# BMS_AFE_-_Thermistors.net
KiCad netlist of a schematic drawn in Altium Designer
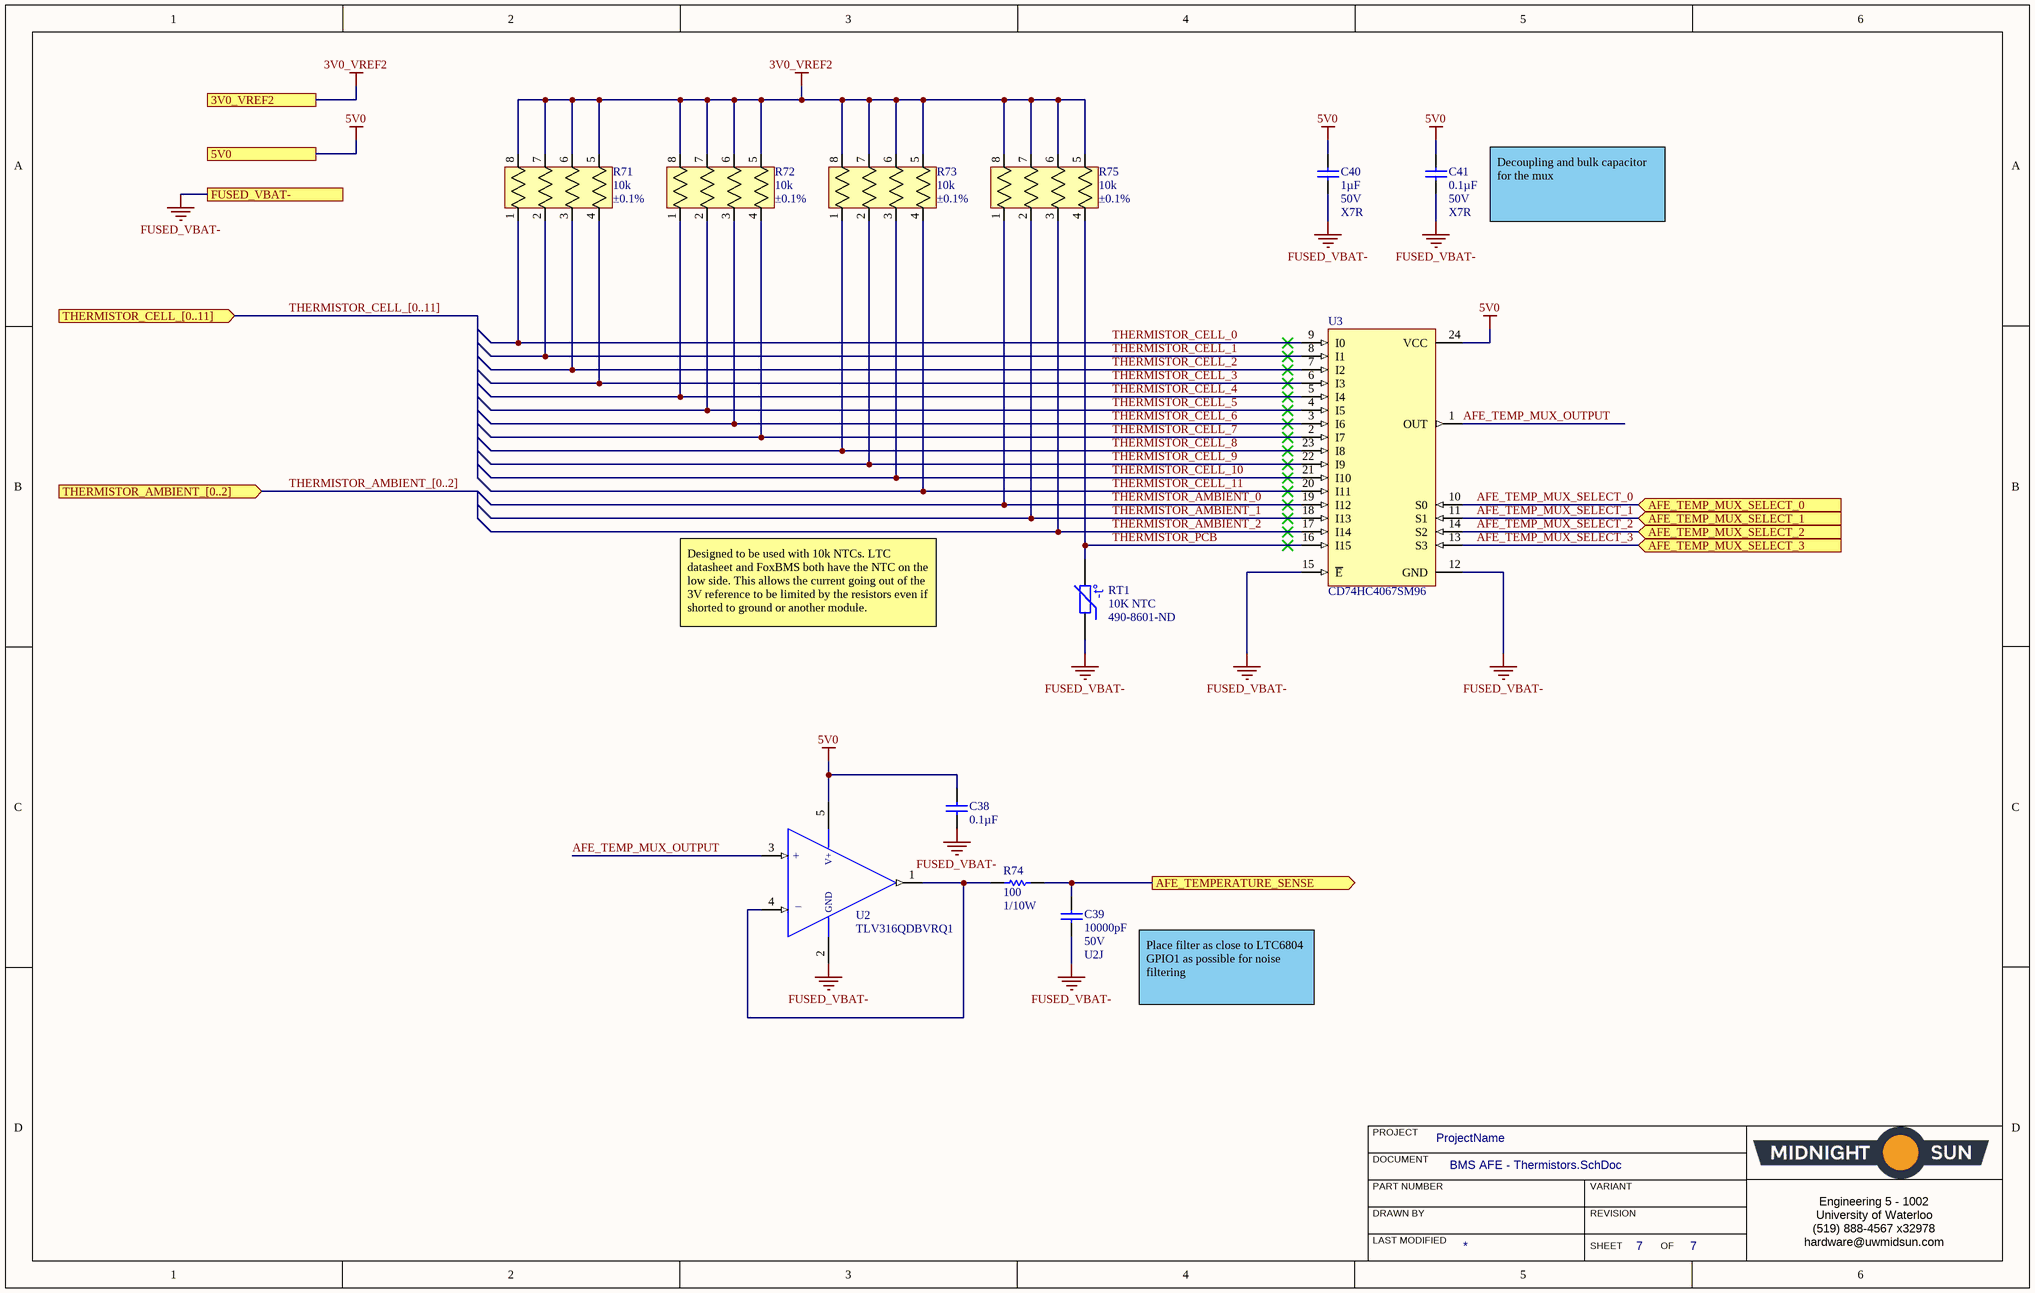
[diagram p0: BMS AFE - Thermistors.SchDoc]

(export (version "E")
  (design (tool "Eeschema 10.0.6"))
  (components
    (comp (ref "C38")
      (value "CAP CER 0.1UF 50V 10% X7R 0603")
      (footprint "CAP, 0603")
      (description "0.10µF ±10% 50V Ceramic Capacitor X7R 0603 (1608 Metric)")
      (fields
        (field (name "TOLERANCE") "±10%")
        (field (name "CAPACITANCE") "0.1µF")
        (field (name "VOLTAGE") "50V")
      )
      (libsource (lib "Schematic Diagrams") (part "CAP CER 0.1UF 50V 10% X7R 0603"))
    )
    (comp (ref "C39")
      (value "CAP CER 10nF 50V 5% X7R 0603")
      (footprint "CAP, 0603")
      (description "10000pF ±5% 50V Ceramic Capacitor U2J 0603 (1608 Metric)")
      (fields
        (field (name "TOLERANCE") "±5%")
        (field (name "CAPACITANCE") "10000pF")
        (field (name "VOLTAGE") "50V")
        (field (name "TEMPERATURE COEFFICIENT") "U2J")
      )
      (libsource (lib "Schematic Diagrams") (part "CAP CER 10nF 50V 5% X7R 0603"))
    )
    (comp (ref "C40")
      (value "CAP CER 1UF 50V 10% X7R 0603")
      (footprint "CAP, 0603")
      (description "1µF ±10% 50V Ceramic Capacitor X7R 0603 (1608 Metric)")
      (fields
        (field (name "TOLERANCE") "±10%")
        (field (name "CAPACITANCE") "1µF")
        (field (name "VOLTAGE") "50V")
        (field (name "TEMPERATURE COEFFICIENT") "X7R")
      )
      (libsource (lib "Schematic Diagrams") (part "CAP CER 1UF 50V 10% X7R 0603"))
    )
    (comp (ref "C41")
      (value "CAP CER 0.1UF 50V 10% X7R 0603")
      (footprint "CAP, 0603")
      (description "0.10µF ±10% 50V Ceramic Capacitor X7R 0603 (1608 Metric)")
      (fields
        (field (name "TOLERANCE") "±10%")
        (field (name "CAPACITANCE") "0.1µF")
        (field (name "VOLTAGE") "50V")
        (field (name "TEMPERATURE COEFFICIENT") "X7R")
      )
      (libsource (lib "Schematic Diagrams") (part "CAP CER 0.1UF 50V 10% X7R 0603"))
    )
    (comp (ref "R71")
      (value "RES ARRAY 10K OHM 0.1% 4RES 1206")
      (footprint "RES ARRAY 4RES 1206")
      (fields
        (field (name "MANUFACTURER") "Vishay Beyschlag")
        (field (name "MANUFACTURER PART NUMBER") "ACASA1002S1002P100")
        (field (name "RESISTANCE (OHMS)") "10k")
        (field (name "TOLERANCE") "±0.1%")
      )
      (libsource (lib "Schematic Diagrams") (part "RES ARRAY 10K OHM 0.1% 4RES 1206"))
    )
    (comp (ref "R72")
      (value "RES ARRAY 10K OHM 0.1% 4RES 1206")
      (footprint "RES ARRAY 4RES 1206")
      (fields
        (field (name "MANUFACTURER") "Vishay Beyschlag")
        (field (name "MANUFACTURER PART NUMBER") "ACASA1002S1002P100")
        (field (name "RESISTANCE (OHMS)") "10k")
        (field (name "TOLERANCE") "±0.1%")
      )
      (libsource (lib "Schematic Diagrams") (part "RES ARRAY 10K OHM 0.1% 4RES 1206"))
    )
    (comp (ref "R73")
      (value "RES ARRAY 10K OHM 0.1% 4RES 1206")
      (footprint "RES ARRAY 4RES 1206")
      (fields
        (field (name "MANUFACTURER") "Vishay Beyschlag")
        (field (name "MANUFACTURER PART NUMBER") "ACASA1002S1002P100")
        (field (name "RESISTANCE (OHMS)") "10k")
        (field (name "TOLERANCE") "±0.1%")
      )
      (libsource (lib "Schematic Diagrams") (part "RES ARRAY 10K OHM 0.1% 4RES 1206"))
    )
    (comp (ref "R74")
      (value "RES 100 OHM 1% 1/10W 0603")
      (footprint "RES, 0603")
      (description "100 Ohm ±1% 0.1W, 1/10W Chip Resistor 0603 (1608 Metric) Moisture Resistant Thick Film")
      (fields
        (field (name "TOLERANCE") "±1%")
        (field (name "RESISTANCE") "100")
        (field (name "POWER") "1/10W")
      )
      (libsource (lib "Schematic Diagrams") (part "RES 100 OHM 1% 1/10W 0603"))
    )
    (comp (ref "R75")
      (value "RES ARRAY 10K OHM 0.1% 4RES 1206")
      (footprint "RES ARRAY 4RES 1206")
      (fields
        (field (name "MANUFACTURER") "Vishay Beyschlag")
        (field (name "MANUFACTURER PART NUMBER") "ACASA1002S1002P100")
        (field (name "RESISTANCE (OHMS)") "10k")
        (field (name "TOLERANCE") "±0.1%")
      )
      (libsource (lib "Schematic Diagrams") (part "RES ARRAY 10K OHM 0.1% 4RES 1206"))
    )
    (comp (ref "RT1")
      (value "10K NTC")
      (footprint "NTC THERMISTOR BEAD")
      (description "NTC Thermistor 10k Bead")
      (fields
        (field (name "MANUFACTURER") "Murata Electronics North America")
        (field (name "MANUFACTURER PART NUMBER") "NXRT15XH103FA1B030")
        (field (name "SUPPLIER PART NUMBER 1") "490-8601-ND")
      )
      (libsource (lib "Schematic Diagrams") (part "NTC THERMISTOR 10K 1% BEAD"))
    )
    (comp (ref "U2")
      (value "IC OP AMP GEN PURPOSE RR 10MHZ SOT-23-5")
      (footprint "IC OP AMP GP RR 10MHZ SOT-23-5")
      (description "General Purpose Amplifier 1 Circuit Rail-to-Rail SOT-23-5")
      (fields (field (name "MANUFACTURER PART NUMBER 1") "TLV316QDBVRQ1"))
      (libsource (lib "Schematic Diagrams") (part "IC OP AMP GEN PURPOSE RR 10MHZ SOT-23-5"))
    )
    (comp (ref "U3")
      (value "IC MUX/DEMUX 1X16 24SSOP")
      (footprint "SOP127P1030X265-24N")
      (description "1 Circuit IC Switch 16:1 160 Ohm 24-SSOP")
      (fields (field (name "MANUFACTURER PART NUMBER 1") "CD74HC4067SM96"))
      (libsource (lib "Schematic Diagrams") (part "IC MUX/DEMUX 1X16 24SSOP"))
    )
  )
  (nets
    (net (code "1") (name "/AFE_TEMPERATURE_SENSE") (class "Default")
      (node (ref "C39") (pin "1") (pinfunction "1_1") (pintype "passive"))
      (node (ref "R74") (pin "2") (pinfunction "2_2") (pintype "passive"))
    )
    (net (code "2") (name "/AFE_TEMP_MUX_OUTPUT") (class "Default")
      (node (ref "U2") (pin "3") (pinfunction "+IN_3") (pintype "input"))
      (node (ref "U3") (pin "1") (pinfunction "OUT_1") (pintype "output"))
    )
    (net (code "3") (name "/AFE_TEMP_MUX_SELECT_0") (class "Default")
      (node (ref "U3") (pin "10") (pinfunction "S0_10") (pintype "input"))
    )
    (net (code "4") (name "/AFE_TEMP_MUX_SELECT_1") (class "Default")
      (node (ref "U3") (pin "11") (pinfunction "S1_11") (pintype "input"))
    )
    (net (code "5") (name "/AFE_TEMP_MUX_SELECT_2") (class "Default")
      (node (ref "U3") (pin "14") (pinfunction "S2_14") (pintype "input"))
    )
    (net (code "6") (name "/AFE_TEMP_MUX_SELECT_3") (class "Default")
      (node (ref "U3") (pin "13") (pinfunction "S3_13") (pintype "input"))
    )
    (net (code "7") (name "/THERMISTOR_AMBIENT_0") (class "Default")
      (node (ref "R75") (pin "1") (pinfunction "1_1") (pintype "passive"))
      (node (ref "U3") (pin "19") (pinfunction "I12_19") (pintype "input"))
    )
    (net (code "8") (name "/THERMISTOR_AMBIENT_1") (class "Default")
      (node (ref "R75") (pin "2") (pinfunction "2_2") (pintype "passive"))
      (node (ref "U3") (pin "18") (pinfunction "I13_18") (pintype "input"))
    )
    (net (code "9") (name "/THERMISTOR_AMBIENT_2") (class "Default")
      (node (ref "R75") (pin "3") (pinfunction "3_3") (pintype "passive"))
      (node (ref "U3") (pin "17") (pinfunction "I14_17") (pintype "input"))
    )
    (net (code "11") (name "/THERMISTOR_CELL_0") (class "Default")
      (node (ref "R71") (pin "1") (pinfunction "1_1") (pintype "passive"))
      (node (ref "U3") (pin "9") (pinfunction "I0_9") (pintype "input"))
    )
    (net (code "12") (name "/THERMISTOR_CELL_1") (class "Default")
      (node (ref "R71") (pin "2") (pinfunction "2_2") (pintype "passive"))
      (node (ref "U3") (pin "8") (pinfunction "I1_8") (pintype "input"))
    )
    (net (code "13") (name "/THERMISTOR_CELL_2") (class "Default")
      (node (ref "R71") (pin "3") (pinfunction "3_3") (pintype "passive"))
      (node (ref "U3") (pin "7") (pinfunction "I2_7") (pintype "input"))
    )
    (net (code "14") (name "/THERMISTOR_CELL_3") (class "Default")
      (node (ref "R71") (pin "4") (pinfunction "4_4") (pintype "passive"))
      (node (ref "U3") (pin "6") (pinfunction "I3_6") (pintype "input"))
    )
    (net (code "15") (name "/THERMISTOR_CELL_4") (class "Default")
      (node (ref "R72") (pin "1") (pinfunction "1_1") (pintype "passive"))
      (node (ref "U3") (pin "5") (pinfunction "I4_5") (pintype "input"))
    )
    (net (code "16") (name "/THERMISTOR_CELL_5") (class "Default")
      (node (ref "R72") (pin "2") (pinfunction "2_2") (pintype "passive"))
      (node (ref "U3") (pin "4") (pinfunction "I5_4") (pintype "input"))
    )
    (net (code "17") (name "/THERMISTOR_CELL_6") (class "Default")
      (node (ref "R72") (pin "3") (pinfunction "3_3") (pintype "passive"))
      (node (ref "U3") (pin "3") (pinfunction "I6_3") (pintype "input"))
    )
    (net (code "18") (name "/THERMISTOR_CELL_7") (class "Default")
      (node (ref "R72") (pin "4") (pinfunction "4_4") (pintype "passive"))
      (node (ref "U3") (pin "2") (pinfunction "I7_2") (pintype "input"))
    )
    (net (code "19") (name "/THERMISTOR_CELL_8") (class "Default")
      (node (ref "R73") (pin "1") (pinfunction "1_1") (pintype "passive"))
      (node (ref "U3") (pin "23") (pinfunction "I8_23") (pintype "input"))
    )
    (net (code "20") (name "/THERMISTOR_CELL_9") (class "Default")
      (node (ref "R73") (pin "2") (pinfunction "2_2") (pintype "passive"))
      (node (ref "U3") (pin "22") (pinfunction "I9_22") (pintype "input"))
    )
    (net (code "21") (name "/THERMISTOR_CELL_10") (class "Default")
      (node (ref "R73") (pin "3") (pinfunction "3_3") (pintype "passive"))
      (node (ref "U3") (pin "21") (pinfunction "I10_21") (pintype "input"))
    )
    (net (code "22") (name "/THERMISTOR_CELL_11") (class "Default")
      (node (ref "R73") (pin "4") (pinfunction "4_4") (pintype "passive"))
      (node (ref "U3") (pin "20") (pinfunction "I11_20") (pintype "input"))
    )
    (net (code "24") (name "/THERMISTOR_PCB") (class "Default")
      (node (ref "R75") (pin "4") (pinfunction "4_4") (pintype "passive"))
      (node (ref "RT1") (pin "2") (pinfunction "2_2") (pintype "passive"))
      (node (ref "U3") (pin "16") (pinfunction "I15_16") (pintype "input"))
    )
    (net (code "25") (name "3V0_VREF2") (class "Default")
      (node (ref "R71") (pin "5") (pinfunction "5_5") (pintype "passive"))
      (node (ref "R71") (pin "6") (pinfunction "6_6") (pintype "passive"))
      (node (ref "R71") (pin "7") (pinfunction "7_7") (pintype "passive"))
      (node (ref "R71") (pin "8") (pinfunction "8_8") (pintype "passive"))
      (node (ref "R72") (pin "5") (pinfunction "5_5") (pintype "passive"))
      (node (ref "R72") (pin "6") (pinfunction "6_6") (pintype "passive"))
      (node (ref "R72") (pin "7") (pinfunction "7_7") (pintype "passive"))
      (node (ref "R72") (pin "8") (pinfunction "8_8") (pintype "passive"))
      (node (ref "R73") (pin "5") (pinfunction "5_5") (pintype "passive"))
      (node (ref "R73") (pin "6") (pinfunction "6_6") (pintype "passive"))
      (node (ref "R73") (pin "7") (pinfunction "7_7") (pintype "passive"))
      (node (ref "R73") (pin "8") (pinfunction "8_8") (pintype "passive"))
      (node (ref "R75") (pin "5") (pinfunction "5_5") (pintype "passive"))
      (node (ref "R75") (pin "6") (pinfunction "6_6") (pintype "passive"))
      (node (ref "R75") (pin "7") (pinfunction "7_7") (pintype "passive"))
      (node (ref "R75") (pin "8") (pinfunction "8_8") (pintype "passive"))
    )
    (net (code "26") (name "5V0") (class "Default")
      (node (ref "C38") (pin "1") (pinfunction "1_1") (pintype "passive"))
      (node (ref "C40") (pin "1") (pinfunction "1_1") (pintype "passive"))
      (node (ref "C41") (pin "1") (pinfunction "1_1") (pintype "passive"))
      (node (ref "U2") (pin "5") (pinfunction "VDD_5") (pintype "power_in"))
      (node (ref "U3") (pin "24") (pinfunction "VCC_24") (pintype "power_in"))
    )
    (net (code "27") (name "FUSED_VBAT-") (class "Default")
      (node (ref "C38") (pin "2") (pinfunction "2_2") (pintype "passive"))
      (node (ref "C39") (pin "2") (pinfunction "2_2") (pintype "passive"))
      (node (ref "C40") (pin "2") (pinfunction "2_2") (pintype "passive"))
      (node (ref "C41") (pin "2") (pinfunction "2_2") (pintype "passive"))
      (node (ref "RT1") (pin "1") (pinfunction "1_1") (pintype "passive"))
      (node (ref "U2") (pin "2") (pinfunction "VSS_2") (pintype "power_in"))
      (node (ref "U3") (pin "12") (pinfunction "GND_12") (pintype "power_in"))
      (node (ref "U3") (pin "15") (pinfunction "~{E}_15") (pintype "input"))
    )
    (net (code "28") (name "Net-(U2--IN)") (class "Default")
      (node (ref "R74") (pin "1") (pinfunction "1_1") (pintype "passive"))
      (node (ref "U2") (pin "1") (pinfunction "OUTPUT_1") (pintype "output"))
      (node (ref "U2") (pin "4") (pinfunction "-IN_4") (pintype "input"))
    )
  )
)
